# Storage.net
KiCad netlist of a schematic drawn in Altium Designer
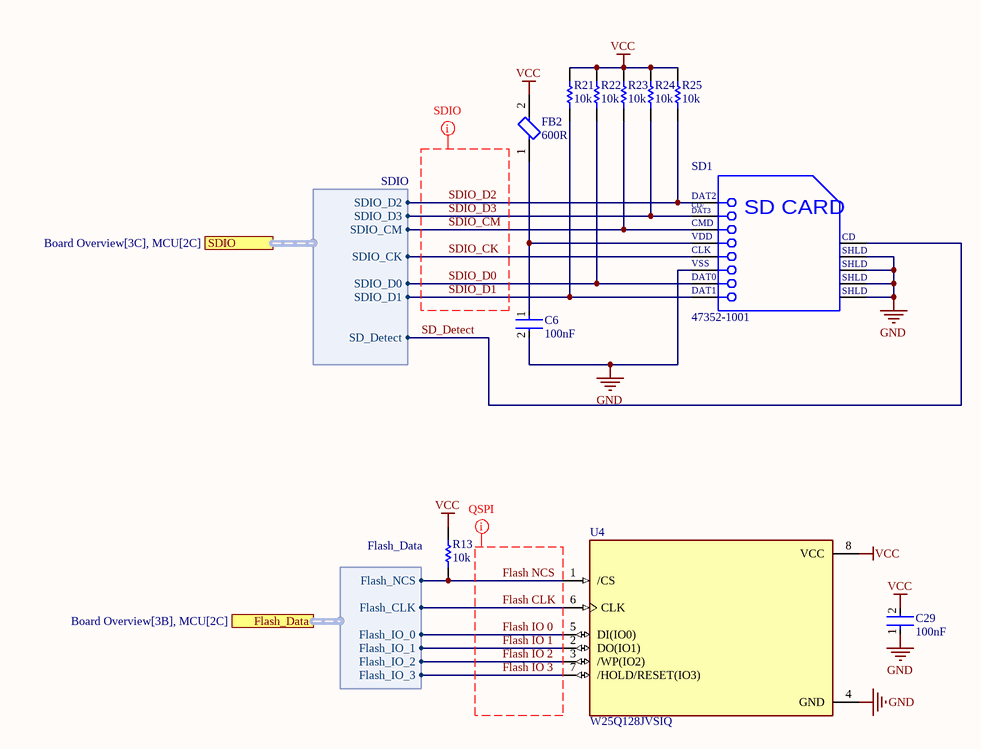
[diagram p0: Storage.SchDoc]

(export (version "E")
  (design (tool "Eeschema 10.0.6"))
  (components
    (comp (ref "C6")
      (value "100nF")
      (footprint "FP-0603-L_1_6_0_15-W_0_81-IPC_C")
      (description "Generic 0603 Capacitor")
      (fields (field (name "LCSC PART #") "C14663") (field (name "TOLERANCE") "10%"))
      (libsource (lib "StrathSEDS") (part "02cd4be3c70576c341d710602a673aa"))
    )
    (comp (ref "C29")
      (value "100nF")
      (footprint "FP-0603-L_1_6_0_15-W_0_81-IPC_C")
      (description "Generic 0603 Capacitor")
      (fields (field (name "LCSC PART #") "C14663") (field (name "TOLERANCE") "10%"))
      (libsource (lib "StrathSEDS") (part "02cd4be3c70576c341d710602a673aa"))
    )
    (comp (ref "FB2")
      (value "600R")
      (footprint "FP-BLM18-0_15-0_1-t0_6-IPC_B")
      (description "0603 600Ω ±25% DCR=0.45Ω 0.2A")
      (fields (field (name "LCSC PART #") "C1002") (field (name "Comment") "GZ1608D601TF"))
      (libsource (lib "StrathSEDS Mach 22") (part "5f30dd21d616792df468990f7003faa"))
    )
    (comp (ref "R13")
      (value "10k")
      (footprint "RESC1609X50X30ML8T20")
      (description "Generic 0603 Resistor")
      (fields (field (name "TOLERANCE") "0%") (field (name "LCSC PART #") "C25804"))
      (libsource (lib "StrathSEDS") (part "RES-2"))
    )
    (comp (ref "R21")
      (value "10k")
      (footprint "RESC1609X50X30ML8T20")
      (description "Generic 0603 Resistor")
      (fields (field (name "TOLERANCE") "0%") (field (name "LCSC PART #") "C25804"))
      (libsource (lib "StrathSEDS") (part "RES-2"))
    )
    (comp (ref "R22")
      (value "10k")
      (footprint "RESC1609X50X30ML8T20")
      (description "Generic 0603 Resistor")
      (fields (field (name "TOLERANCE") "0%") (field (name "LCSC PART #") "C25804"))
      (libsource (lib "StrathSEDS") (part "RES-2"))
    )
    (comp (ref "R23")
      (value "10k")
      (footprint "RESC1609X50X30ML8T20")
      (description "Generic 0603 Resistor")
      (fields (field (name "TOLERANCE") "0%") (field (name "LCSC PART #") "C25804"))
      (libsource (lib "StrathSEDS") (part "RES-2"))
    )
    (comp (ref "R24")
      (value "10k")
      (footprint "RESC1609X50X30ML8T20")
      (description "Generic 0603 Resistor")
      (fields (field (name "TOLERANCE") "0%") (field (name "LCSC PART #") "C25804"))
      (libsource (lib "StrathSEDS") (part "RES-2"))
    )
    (comp (ref "R25")
      (value "10k")
      (footprint "RESC1609X50X30ML8T20")
      (description "Generic 0603 Resistor")
      (fields (field (name "TOLERANCE") "0%") (field (name "LCSC PART #") "C25804"))
      (libsource (lib "StrathSEDS") (part "RES-2"))
    )
    (comp (ref "SD1")
      (value "47352-1001")
      (footprint "MOLX-473521001_V")
      (description "Conn Micro SD Card HDR 8 POS 1.1mm Solder RA SMD Embossed T/R 0.5A/Contact")
      (fields (field (name "LCSC PART #") "C293569"))
      (libsource (lib "StrathSEDS") (part "CN-SD-8-1SW-4S"))
    )
    (comp (ref "U4")
      (value "W25Q128JVSIQ")
      (footprint "SOIC127P790X216-8N")
      (description "FLASH - NOR Memory IC 128Mb (16M x 8) SPI - Quad I/O, QPI, DTR 133 MHz 8-SOIC")
      (fields (field (name "MF") "Winbond Electronics") (field (name "LCSC PART #") "C97521"))
      (libsource (lib "StrathSEDS") (part "W25Q128JVSIQ"))
    )
  )
  (nets
    (net (code "3") (name "/Flash CLK") (class "Default")
      (node (ref "U4") (pin "6") (pinfunction "CLK_6") (pintype "input"))
    )
    (net (code "4") (name "/Flash IO 0") (class "Default")
      (node (ref "U4") (pin "5") (pinfunction "DI(IO0)_5") (pintype "bidirectional"))
    )
    (net (code "5") (name "/Flash IO 1") (class "Default")
      (node (ref "U4") (pin "2") (pinfunction "DO(IO1)_2") (pintype "bidirectional"))
    )
    (net (code "6") (name "/Flash IO 2") (class "Default")
      (node (ref "U4") (pin "3") (pinfunction "/WP(IO2)_3") (pintype "bidirectional"))
    )
    (net (code "7") (name "/Flash IO 3") (class "Default")
      (node (ref "U4") (pin "7") (pinfunction "/HOLD/RESET(IO3)_7") (pintype "bidirectional"))
    )
    (net (code "8") (name "/Flash NCS") (class "Default")
      (node (ref "R13") (pin "1") (pinfunction "1_1") (pintype "passive"))
      (node (ref "U4") (pin "1") (pinfunction "/CS_1") (pintype "input"))
    )
    (net (code "9") (name "/SDIO_CK") (class "Default")
      (node (ref "SD1") (pin "5") (pinfunction "CLK_5") (pintype "passive"))
    )
    (net (code "10") (name "/SDIO_CM") (class "Default")
      (node (ref "R23") (pin "1") (pinfunction "1_1") (pintype "passive"))
      (node (ref "SD1") (pin "3") (pinfunction "CMD_3") (pintype "passive"))
    )
    (net (code "11") (name "/SDIO_D0") (class "Default")
      (node (ref "R22") (pin "1") (pinfunction "1_1") (pintype "passive"))
      (node (ref "SD1") (pin "7") (pinfunction "DAT0_7") (pintype "passive"))
    )
    (net (code "12") (name "/SDIO_D1") (class "Default")
      (node (ref "R21") (pin "1") (pinfunction "1_1") (pintype "passive"))
      (node (ref "SD1") (pin "8") (pinfunction "DAT1_8") (pintype "passive"))
    )
    (net (code "13") (name "/SDIO_D2") (class "Default")
      (node (ref "R25") (pin "1") (pinfunction "1_1") (pintype "passive"))
      (node (ref "SD1") (pin "1") (pinfunction "DAT2_1") (pintype "passive"))
    )
    (net (code "14") (name "/SDIO_D3") (class "Default")
      (node (ref "R24") (pin "1") (pinfunction "1_1") (pintype "passive"))
      (node (ref "SD1") (pin "2") (pinfunction "CD/DAT3_2") (pintype "passive"))
    )
    (net (code "15") (name "/SD_Detect") (class "Default")
      (node (ref "SD1") (pin "9") (pinfunction "CD_9") (pintype "passive"))
    )
    (net (code "18") (name "GND") (class "Default")
      (node (ref "C29") (pin "1") (pinfunction "1_1") (pintype "passive"))
      (node (ref "C6") (pin "2") (pinfunction "2_2") (pintype "passive"))
      (node (ref "SD1") (pin "10") (pinfunction "SHLD_10") (pintype "passive"))
      (node (ref "SD1") (pin "11") (pinfunction "SHLD_11") (pintype "passive"))
      (node (ref "SD1") (pin "12") (pinfunction "SHLD_12") (pintype "passive"))
      (node (ref "SD1") (pin "13") (pinfunction "SHLD_13") (pintype "passive"))
      (node (ref "SD1") (pin "6") (pinfunction "VSS_6") (pintype "passive"))
      (node (ref "U4") (pin "4") (pinfunction "GND_4") (pintype "power_in"))
    )
    (net (code "19") (name "Net-(SD1-VDD)") (class "Default")
      (node (ref "C6") (pin "1") (pinfunction "1_1") (pintype "passive"))
      (node (ref "FB2") (pin "1") (pinfunction "1_1") (pintype "passive"))
      (node (ref "SD1") (pin "4") (pinfunction "VDD_4") (pintype "passive"))
    )
    (net (code "20") (name "VCC") (class "Default")
      (node (ref "C29") (pin "2") (pinfunction "2_2") (pintype "passive"))
      (node (ref "FB2") (pin "2") (pinfunction "2_2") (pintype "passive"))
      (node (ref "R13") (pin "2") (pinfunction "2_2") (pintype "passive"))
      (node (ref "R21") (pin "2") (pinfunction "2_2") (pintype "passive"))
      (node (ref "R22") (pin "2") (pinfunction "2_2") (pintype "passive"))
      (node (ref "R23") (pin "2") (pinfunction "2_2") (pintype "passive"))
      (node (ref "R24") (pin "2") (pinfunction "2_2") (pintype "passive"))
      (node (ref "R25") (pin "2") (pinfunction "2_2") (pintype "passive"))
      (node (ref "U4") (pin "8") (pinfunction "VCC_8") (pintype "power_in"))
    )
  )
)
